# ESP8266.net
KiCad netlist of a schematic drawn in Altium Designer
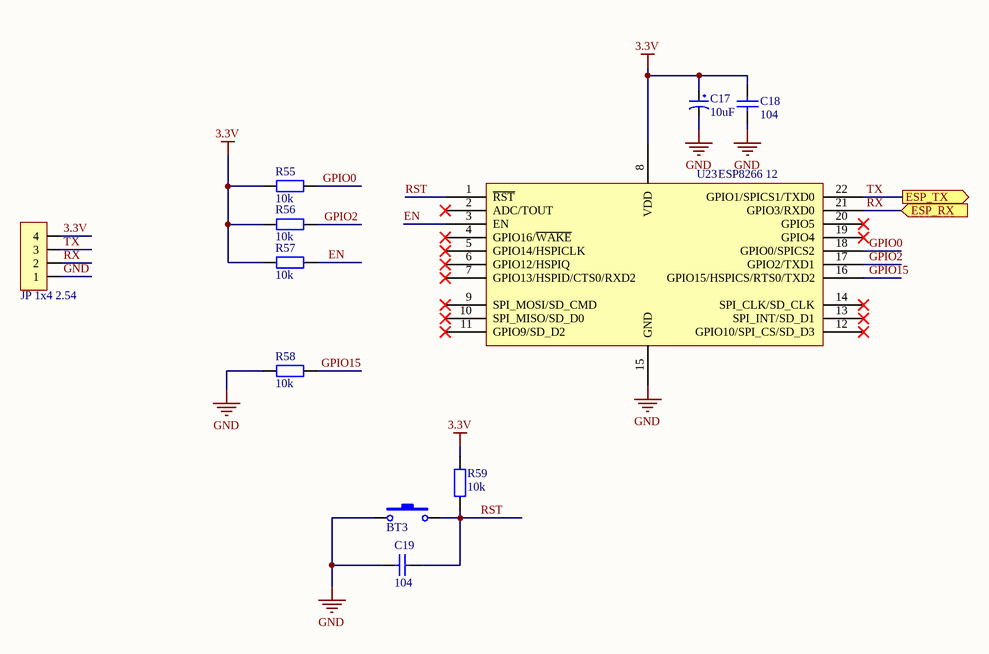
[diagram p0: ESP8266.SchDoc]

(export (version "E")
  (design (tool "Eeschema 10.0.6"))
  (components
    (comp (ref "BT3")
      (value "Nut Nhan 2 Chan SMD 3x6x2.5")
      (footprint "Nut Nhan 2 Chan SMD 3x6x2.5")
      (libsource (lib "Altium_Lib_by_KhueNguyenCreator") (part "Nut Nhan 2 Chan SMD 3x6x2.5"))
    )
    (comp (ref "C17")
      (value "10uF")
      (footprint "tu tantalum smd3216")
      (description "Dán")
      (libsource (lib "Altium_Lib_by_KhueNguyenCreator") (part "Tu tantalum 10uF 16V SMD3216"))
    )
    (comp (ref "C18")
      (value "104")
      (footprint "tu 0603")
      (description "Dán")
      (libsource (lib "Altium_Lib_by_KhueNguyenCreator") (part "Tu 0603 104 50V 10%"))
    )
    (comp (ref "C19")
      (value "104")
      (footprint "tu 0603")
      (description "Dán")
      (libsource (lib "Altium_Lib_by_KhueNguyenCreator") (part "Tu 0603 104 50V 10%"))
    )
    (comp (ref "JP2")
      (value "JP 1x4 2.54")
      (footprint "JP 1x4 DT")
      (description "Cắm")
      (libsource (lib "Altium_Lib_by_KhueNguyenCreator") (part "JP 1x4 2.54 Duc Thang"))
    )
    (comp (ref "R55")
      (value "10k")
      (footprint "tro smd 0805")
      (description "Dán")
      (libsource (lib "Altium_Lib_by_KhueNguyenCreator") (part "Tro 0805 5% 10k"))
    )
    (comp (ref "R56")
      (value "10k")
      (footprint "tro smd 0805")
      (description "Dán")
      (libsource (lib "Altium_Lib_by_KhueNguyenCreator") (part "Tro 0805 5% 10k"))
    )
    (comp (ref "R57")
      (value "10k")
      (footprint "tro smd 0805")
      (description "Dán")
      (libsource (lib "Altium_Lib_by_KhueNguyenCreator") (part "Tro 0805 5% 10k"))
    )
    (comp (ref "R58")
      (value "10k")
      (footprint "tro smd 0805")
      (description "Dán")
      (libsource (lib "Altium_Lib_by_KhueNguyenCreator") (part "Tro 0805 5% 10k"))
    )
    (comp (ref "R59")
      (value "10k")
      (footprint "tro smd 0805")
      (description "Dán")
      (libsource (lib "Altium_Lib_by_KhueNguyenCreator") (part "Tro 0805 5% 10k"))
    )
    (comp (ref "U23")
      (value "ESP8266 12")
      (footprint "ESP8266 12")
      (description "ESP8266 12 22 Pin")
      (libsource (lib "Altium_Lib_by_KhueNguyenCreator") (part "ESP8266 12"))
    )
  )
  (nets
    (net (code "1") (name "/EN") (class "Default")
      (node (ref "R57") (pin "2") (pinfunction "2_2") (pintype "passive"))
      (node (ref "U23") (pin "3") (pinfunction "EN_3") (pintype "passive"))
    )
    (net (code "2") (name "/GPIO0") (class "Default")
      (node (ref "R55") (pin "2") (pinfunction "2_2") (pintype "passive"))
      (node (ref "U23") (pin "18") (pinfunction "GPIO0/SPICS2_18") (pintype "passive"))
    )
    (net (code "3") (name "/GPIO2") (class "Default")
      (node (ref "R56") (pin "2") (pinfunction "2_2") (pintype "passive"))
      (node (ref "U23") (pin "17") (pinfunction "GPIO2/TXD1_17") (pintype "passive"))
    )
    (net (code "4") (name "/GPIO15") (class "Default")
      (node (ref "R58") (pin "2") (pinfunction "2_2") (pintype "passive"))
      (node (ref "U23") (pin "16") (pinfunction "GPIO15/HSPICS/RTS0/TXD2_16") (pintype "passive"))
    )
    (net (code "5") (name "/RST") (class "Default")
      (node (ref "BT3") (pin "2") (pinfunction "2_2") (pintype "passive"))
      (node (ref "C19") (pin "2") (pinfunction "2_2") (pintype "passive"))
      (node (ref "R59") (pin "1") (pinfunction "1_1") (pintype "passive"))
      (node (ref "U23") (pin "1") (pinfunction "~{RST}_1") (pintype "passive"))
    )
    (net (code "6") (name "/RX") (class "Default")
      (node (ref "JP2") (pin "2") (pinfunction "2_2") (pintype "passive"))
      (node (ref "U23") (pin "21") (pinfunction "GPIO3/RXD0_21") (pintype "passive"))
    )
    (net (code "7") (name "/TX") (class "Default")
      (node (ref "JP2") (pin "3") (pinfunction "3_3") (pintype "passive"))
      (node (ref "U23") (pin "22") (pinfunction "GPIO1/SPICS1/TXD0_22") (pintype "passive"))
    )
    (net (code "8") (name "3.3V") (class "Default")
      (node (ref "C17") (pin "1") (pinfunction "1_1") (pintype "passive"))
      (node (ref "C18") (pin "1") (pinfunction "1_1") (pintype "passive"))
      (node (ref "JP2") (pin "4") (pinfunction "4_4") (pintype "passive"))
      (node (ref "R55") (pin "1") (pinfunction "1_1") (pintype "passive"))
      (node (ref "R56") (pin "1") (pinfunction "1_1") (pintype "passive"))
      (node (ref "R57") (pin "1") (pinfunction "1_1") (pintype "passive"))
      (node (ref "R59") (pin "2") (pinfunction "2_2") (pintype "passive"))
      (node (ref "U23") (pin "8") (pinfunction "VDD_8") (pintype "passive"))
    )
    (net (code "9") (name "GND") (class "Default")
      (node (ref "BT3") (pin "1") (pinfunction "1_1") (pintype "passive"))
      (node (ref "C17") (pin "2") (pinfunction "2_2") (pintype "passive"))
      (node (ref "C18") (pin "2") (pinfunction "2_2") (pintype "passive"))
      (node (ref "C19") (pin "1") (pinfunction "1_1") (pintype "passive"))
      (node (ref "JP2") (pin "1") (pinfunction "1_1") (pintype "passive"))
      (node (ref "R58") (pin "1") (pinfunction "1_1") (pintype "passive"))
      (node (ref "U23") (pin "15") (pinfunction "GND_15") (pintype "passive"))
    )
    (net (code "10") (name "unconnected-(U23-ADC{slash}TOUT-Pad2)") (class "Default")
      (node (ref "U23") (pin "2") (pinfunction "ADC/TOUT_2") (pintype "passive+no_connect"))
    )
    (net (code "11") (name "unconnected-(U23-GPIO4-Pad19)") (class "Default")
      (node (ref "U23") (pin "19") (pinfunction "GPIO4_19") (pintype "passive+no_connect"))
    )
    (net (code "12") (name "unconnected-(U23-GPIO5-Pad20)") (class "Default")
      (node (ref "U23") (pin "20") (pinfunction "GPIO5_20") (pintype "passive+no_connect"))
    )
    (net (code "13") (name "unconnected-(U23-GPIO9{slash}SD_D2-Pad11)") (class "Default")
      (node (ref "U23") (pin "11") (pinfunction "GPIO9/SD_D2_11") (pintype "passive+no_connect"))
    )
    (net (code "14") (name "unconnected-(U23-GPIO10{slash}SPI_CS{slash}SD_D3-Pad12)") (class "Default")
      (node (ref "U23") (pin "12") (pinfunction "GPIO10/SPI_CS/SD_D3_12") (pintype "passive+no_connect"))
    )
    (net (code "15") (name "unconnected-(U23-GPIO12{slash}HSPIQ-Pad6)") (class "Default")
      (node (ref "U23") (pin "6") (pinfunction "GPIO12/HSPIQ_6") (pintype "passive+no_connect"))
    )
    (net (code "16") (name "unconnected-(U23-GPIO13{slash}HSPID{slash}CTS0{slash}RXD2-Pad7)") (class "Default")
      (node (ref "U23") (pin "7") (pinfunction "GPIO13/HSPID/CTS0/RXD2_7") (pintype "passive+no_connect"))
    )
    (net (code "17") (name "unconnected-(U23-GPIO14{slash}HSPICLK-Pad5)") (class "Default")
      (node (ref "U23") (pin "5") (pinfunction "GPIO14/HSPICLK_5") (pintype "passive+no_connect"))
    )
    (net (code "18") (name "unconnected-(U23-GPIO16{slash}~{WAKE}-Pad4)") (class "Default")
      (node (ref "U23") (pin "4") (pinfunction "GPIO16/~{WAKE}_4") (pintype "passive+no_connect"))
    )
    (net (code "19") (name "unconnected-(U23-SPI_CLK{slash}SD_CLK-Pad14)") (class "Default")
      (node (ref "U23") (pin "14") (pinfunction "SPI_CLK/SD_CLK_14") (pintype "passive+no_connect"))
    )
    (net (code "20") (name "unconnected-(U23-SPI_INT{slash}SD_D1-Pad13)") (class "Default")
      (node (ref "U23") (pin "13") (pinfunction "SPI_INT/SD_D1_13") (pintype "passive+no_connect"))
    )
    (net (code "21") (name "unconnected-(U23-SPI_MISO{slash}SD_D0-Pad10)") (class "Default")
      (node (ref "U23") (pin "10") (pinfunction "SPI_MISO/SD_D0_10") (pintype "passive+no_connect"))
    )
    (net (code "22") (name "unconnected-(U23-SPI_MOSI{slash}SD_CMD-Pad9)") (class "Default")
      (node (ref "U23") (pin "9") (pinfunction "SPI_MOSI/SD_CMD_9") (pintype "passive+no_connect"))
    )
  )
)
